# I2C_Messenger_r1.net
KiCad netlist of a schematic drawn in EAGLE
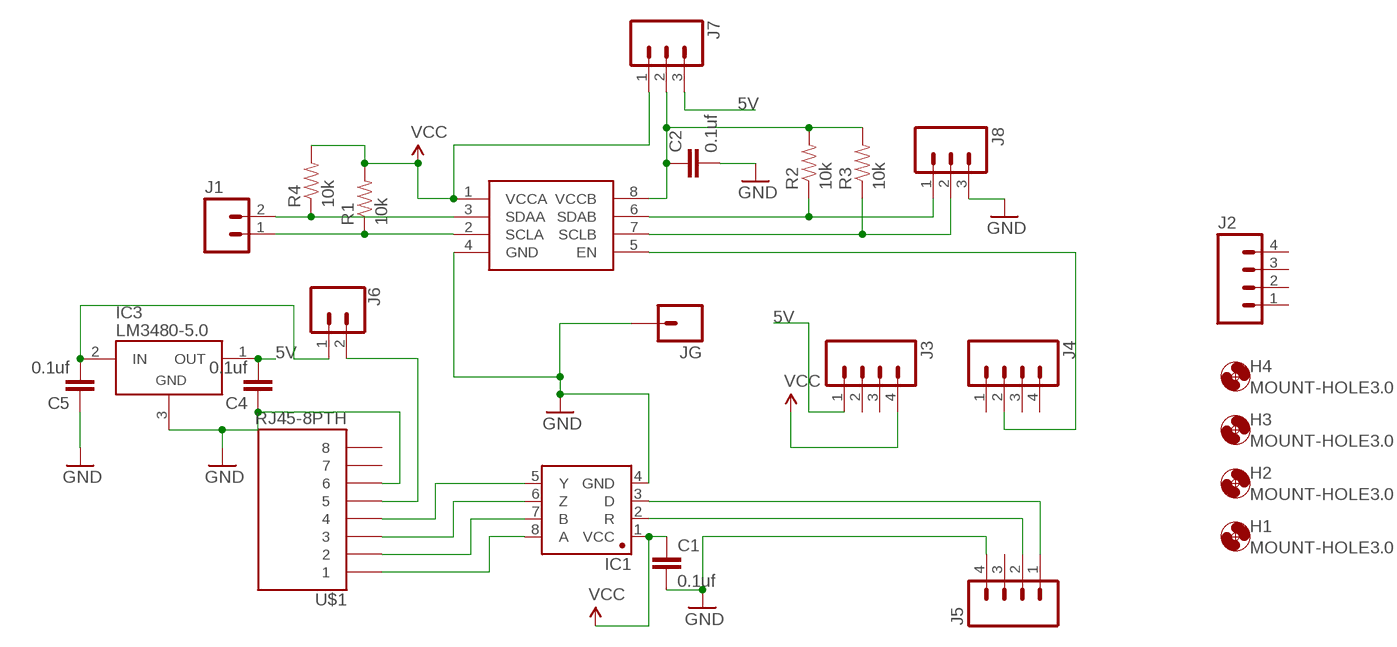
[diagram p0: schematic, sheet 1]

(export (version "E")
  (design (tool "Eeschema 10.0.6"))
  (components
    (comp (ref "C1")
      (value "0.1uf")
      (footprint "eagle-import:1206")
      (libsource (lib "eagle-import") (part "CAP1206"))
    )
    (comp (ref "C2")
      (value "0.1uf")
      (footprint "eagle-import:1206")
      (libsource (lib "eagle-import") (part "CAP1206"))
    )
    (comp (ref "C4")
      (value "0.1uf")
      (footprint "eagle-import:1206")
      (libsource (lib "eagle-import") (part "CAP1206"))
    )
    (comp (ref "C5")
      (value "0.1uf")
      (footprint "eagle-import:1206")
      (libsource (lib "eagle-import") (part "CAP1206"))
    )
    (comp (ref "H1")
      (value "MOUNT-HOLE3.0")
      (footprint "eagle-import:3,0")
      (libsource (lib "eagle-import") (part "MOUNT-HOLE3.0"))
    )
    (comp (ref "H2")
      (value "MOUNT-HOLE3.0")
      (footprint "eagle-import:3,0")
      (libsource (lib "eagle-import") (part "MOUNT-HOLE3.0"))
    )
    (comp (ref "H3")
      (value "MOUNT-HOLE3.0")
      (footprint "eagle-import:3,0")
      (libsource (lib "eagle-import") (part "MOUNT-HOLE3.0"))
    )
    (comp (ref "H4")
      (value "MOUNT-HOLE3.0")
      (footprint "eagle-import:3,0")
      (libsource (lib "eagle-import") (part "MOUNT-HOLE3.0"))
    )
    (comp (ref "IC1")
      (value "SN65HVD31DR")
      (footprint "eagle-import:SO08")
      (libsource (lib "eagle-import") (part "SN65HVD31DR"))
    )
    (comp (ref "IC2")
      (value "PCA9517")
      (footprint "eagle-import:SO-08")
      (libsource (lib "eagle-import") (part "PCA9517"))
    )
    (comp (ref "IC3")
      (value "LM3480-5.0")
      (footprint "eagle-import:SOT-23-3")
      (libsource (lib "eagle-import") (part "LM3480-5.0"))
    )
    (comp (ref "J1")
      (value "M02PTH")
      (footprint "eagle-import:1X02@1")
      (libsource (lib "eagle-import") (part "M02PTH"))
    )
    (comp (ref "J2")
      (value "M04PTH")
      (footprint "eagle-import:1X04")
      (libsource (lib "eagle-import") (part "M04PTH"))
    )
    (comp (ref "J3")
      (value "M04PTH")
      (footprint "eagle-import:1X04")
      (libsource (lib "eagle-import") (part "M04PTH"))
    )
    (comp (ref "J4")
      (value "M04PTH")
      (footprint "eagle-import:1X04")
      (libsource (lib "eagle-import") (part "M04PTH"))
    )
    (comp (ref "J5")
      (value "M04PTH")
      (footprint "eagle-import:1X04")
      (libsource (lib "eagle-import") (part "M04PTH"))
    )
    (comp (ref "J6")
      (value "CONN_02")
      (footprint "eagle-import:1X02")
      (libsource (lib "eagle-import") (part "CONN_02"))
    )
    (comp (ref "J7")
      (value "M03PTH")
      (footprint "eagle-import:1X03")
      (libsource (lib "eagle-import") (part "M03PTH"))
    )
    (comp (ref "J8")
      (value "M03SCREW_LOCK")
      (footprint "eagle-import:SCREWTERMINAL-3.5MM-3_LOCK.007S")
      (libsource (lib "eagle-import") (part "M03SCREW_LOCK"))
    )
    (comp (ref "JG")
      (value "M01PTH")
      (footprint "eagle-import:1X01")
      (libsource (lib "eagle-import") (part "M01PTH"))
    )
    (comp (ref "R1")
      (value "10k")
      (footprint "eagle-import:1206")
      (libsource (lib "eagle-import") (part "RESISTOR1206"))
    )
    (comp (ref "R2")
      (value "10k")
      (footprint "eagle-import:1206")
      (libsource (lib "eagle-import") (part "RESISTOR1206"))
    )
    (comp (ref "R3")
      (value "10k")
      (footprint "eagle-import:1206")
      (libsource (lib "eagle-import") (part "RESISTOR1206"))
    )
    (comp (ref "R4")
      (value "10k")
      (footprint "eagle-import:1206")
      (libsource (lib "eagle-import") (part "RESISTOR1206"))
    )
    (comp (ref "U$1")
      (value "RJ45-8PTH")
      (footprint "eagle-import:RJ45-8")
      (libsource (lib "eagle-import") (part "RJ45-8PTH"))
    )
  )
  (nets
    (net (code "1") (name "/5V") (class "Default")
      (node (ref "C4") (pin "2") (pinfunction "2_2") (pintype "passive"))
      (node (ref "IC3") (pin "1") (pinfunction "OUT_1") (pintype "power_in"))
      (node (ref "J3") (pin "1") (pinfunction "1_1") (pintype "passive"))
      (node (ref "J7") (pin "3") (pinfunction "3_3") (pintype "passive"))
    )
    (net (code "2") (name "GND") (class "Default")
      (node (ref "C1") (pin "2") (pinfunction "2_2") (pintype "passive"))
      (node (ref "C2") (pin "2") (pinfunction "2_2") (pintype "passive"))
      (node (ref "C4") (pin "1") (pinfunction "1_1") (pintype "passive"))
      (node (ref "C5") (pin "1") (pinfunction "1_1") (pintype "passive"))
      (node (ref "IC1") (pin "4") (pinfunction "GND_4") (pintype "bidirectional"))
      (node (ref "IC2") (pin "4") (pinfunction "GND_4") (pintype "bidirectional"))
      (node (ref "IC3") (pin "3") (pinfunction "GND_3") (pintype "power_in"))
      (node (ref "J5") (pin "4") (pinfunction "4_4") (pintype "passive"))
      (node (ref "J8") (pin "3") (pinfunction "3_3") (pintype "passive"))
      (node (ref "JG") (pin "1") (pinfunction "1_1") (pintype "passive"))
      (node (ref "U$1") (pin "6") (pinfunction "6_6") (pintype "bidirectional"))
    )
    (net (code "3") (name "Net-(IC1-A)") (class "Default")
      (node (ref "IC1") (pin "8") (pinfunction "A_8") (pintype "bidirectional"))
      (node (ref "U$1") (pin "1") (pinfunction "1_1") (pintype "bidirectional"))
    )
    (net (code "4") (name "Net-(IC1-B)") (class "Default")
      (node (ref "IC1") (pin "7") (pinfunction "B_7") (pintype "bidirectional"))
      (node (ref "U$1") (pin "2") (pinfunction "2_2") (pintype "bidirectional"))
    )
    (net (code "5") (name "Net-(IC1-D)") (class "Default")
      (node (ref "IC1") (pin "3") (pinfunction "D_3") (pintype "bidirectional"))
      (node (ref "J5") (pin "1") (pinfunction "1_1") (pintype "passive"))
    )
    (net (code "6") (name "Net-(IC1-R)") (class "Default")
      (node (ref "IC1") (pin "2") (pinfunction "R_2") (pintype "bidirectional"))
      (node (ref "J5") (pin "2") (pinfunction "2_2") (pintype "passive"))
    )
    (net (code "7") (name "Net-(IC1-Y)") (class "Default")
      (node (ref "IC1") (pin "5") (pinfunction "Y_5") (pintype "bidirectional"))
      (node (ref "U$1") (pin "4") (pinfunction "4_4") (pintype "bidirectional"))
    )
    (net (code "8") (name "Net-(IC1-Z)") (class "Default")
      (node (ref "IC1") (pin "6") (pinfunction "Z_6") (pintype "bidirectional"))
      (node (ref "U$1") (pin "3") (pinfunction "3_3") (pintype "bidirectional"))
    )
    (net (code "9") (name "Net-(IC2-EN)") (class "Default")
      (node (ref "IC2") (pin "5") (pinfunction "EN_5") (pintype "bidirectional"))
      (node (ref "J4") (pin "2") (pinfunction "2_2") (pintype "passive"))
    )
    (net (code "10") (name "Net-(IC2-SCLA)") (class "Default")
      (node (ref "IC2") (pin "2") (pinfunction "SCLA_2") (pintype "bidirectional"))
      (node (ref "J1") (pin "1") (pinfunction "1_1") (pintype "passive"))
      (node (ref "R1") (pin "1") (pinfunction "1_1") (pintype "passive"))
    )
    (net (code "11") (name "Net-(IC2-SCLB)") (class "Default")
      (node (ref "IC2") (pin "7") (pinfunction "SCLB_7") (pintype "bidirectional"))
      (node (ref "J8") (pin "2") (pinfunction "2_2") (pintype "passive"))
      (node (ref "R3") (pin "1") (pinfunction "1_1") (pintype "passive"))
    )
    (net (code "12") (name "Net-(IC2-SDAA)") (class "Default")
      (node (ref "IC2") (pin "3") (pinfunction "SDAA_3") (pintype "bidirectional"))
      (node (ref "J1") (pin "2") (pinfunction "2_2") (pintype "passive"))
      (node (ref "R4") (pin "1") (pinfunction "1_1") (pintype "passive"))
    )
    (net (code "13") (name "Net-(IC2-SDAB)") (class "Default")
      (node (ref "IC2") (pin "6") (pinfunction "SDAB_6") (pintype "bidirectional"))
      (node (ref "J8") (pin "1") (pinfunction "1_1") (pintype "passive"))
      (node (ref "R2") (pin "1") (pinfunction "1_1") (pintype "passive"))
    )
    (net (code "14") (name "Net-(IC2-VCCB)") (class "Default")
      (node (ref "C2") (pin "1") (pinfunction "1_1") (pintype "passive"))
      (node (ref "IC2") (pin "8") (pinfunction "VCCB_8") (pintype "bidirectional"))
      (node (ref "J7") (pin "2") (pinfunction "2_2") (pintype "passive"))
      (node (ref "R2") (pin "2") (pinfunction "2_2") (pintype "passive"))
      (node (ref "R3") (pin "2") (pinfunction "2_2") (pintype "passive"))
    )
    (net (code "15") (name "Net-(IC3-IN)") (class "Default")
      (node (ref "C5") (pin "2") (pinfunction "2_2") (pintype "passive"))
      (node (ref "IC3") (pin "2") (pinfunction "IN_2") (pintype "power_in"))
      (node (ref "J6") (pin "1") (pinfunction "1_1") (pintype "passive"))
    )
    (net (code "16") (name "Net-(J6-Pad2)") (class "Default")
      (node (ref "J6") (pin "2") (pinfunction "2_2") (pintype "passive"))
      (node (ref "U$1") (pin "5") (pinfunction "5_5") (pintype "bidirectional"))
    )
    (net (code "17") (name "VCC") (class "Default")
      (node (ref "C1") (pin "1") (pinfunction "1_1") (pintype "passive"))
      (node (ref "IC1") (pin "1") (pinfunction "VCC_1") (pintype "bidirectional"))
      (node (ref "IC2") (pin "1") (pinfunction "VCCA_1") (pintype "bidirectional"))
      (node (ref "J3") (pin "4") (pinfunction "4_4") (pintype "passive"))
      (node (ref "J7") (pin "1") (pinfunction "1_1") (pintype "passive"))
      (node (ref "R1") (pin "2") (pinfunction "2_2") (pintype "passive"))
      (node (ref "R4") (pin "2") (pinfunction "2_2") (pintype "passive"))
    )
    (net (code "18") (name "unconnected-(J2-Pad1)") (class "Default")
      (node (ref "J2") (pin "1") (pinfunction "1_1") (pintype "passive"))
    )
    (net (code "19") (name "unconnected-(J2-Pad2)") (class "Default")
      (node (ref "J2") (pin "2") (pinfunction "2_2") (pintype "passive"))
    )
    (net (code "20") (name "unconnected-(J2-Pad3)") (class "Default")
      (node (ref "J2") (pin "3") (pinfunction "3_3") (pintype "passive"))
    )
    (net (code "21") (name "unconnected-(J2-Pad4)") (class "Default")
      (node (ref "J2") (pin "4") (pinfunction "4_4") (pintype "passive"))
    )
    (net (code "22") (name "unconnected-(J3-Pad2)") (class "Default")
      (node (ref "J3") (pin "2") (pinfunction "2_2") (pintype "passive"))
    )
    (net (code "23") (name "unconnected-(J3-Pad3)") (class "Default")
      (node (ref "J3") (pin "3") (pinfunction "3_3") (pintype "passive"))
    )
    (net (code "24") (name "unconnected-(J4-Pad1)") (class "Default")
      (node (ref "J4") (pin "1") (pinfunction "1_1") (pintype "passive"))
    )
    (net (code "25") (name "unconnected-(J4-Pad3)") (class "Default")
      (node (ref "J4") (pin "3") (pinfunction "3_3") (pintype "passive"))
    )
    (net (code "26") (name "unconnected-(J4-Pad4)") (class "Default")
      (node (ref "J4") (pin "4") (pinfunction "4_4") (pintype "passive"))
    )
    (net (code "27") (name "unconnected-(J5-Pad3)") (class "Default")
      (node (ref "J5") (pin "3") (pinfunction "3_3") (pintype "passive"))
    )
    (net (code "28") (name "unconnected-(U$1-Pad7)") (class "Default")
      (node (ref "U$1") (pin "7") (pinfunction "7_7") (pintype "bidirectional"))
    )
    (net (code "29") (name "unconnected-(U$1-Pad8)") (class "Default")
      (node (ref "U$1") (pin "8") (pinfunction "8_8") (pintype "bidirectional"))
    )
  )
)
